# Wiring-Board-Nano.net
KiCad netlist of a schematic drawn in EAGLE
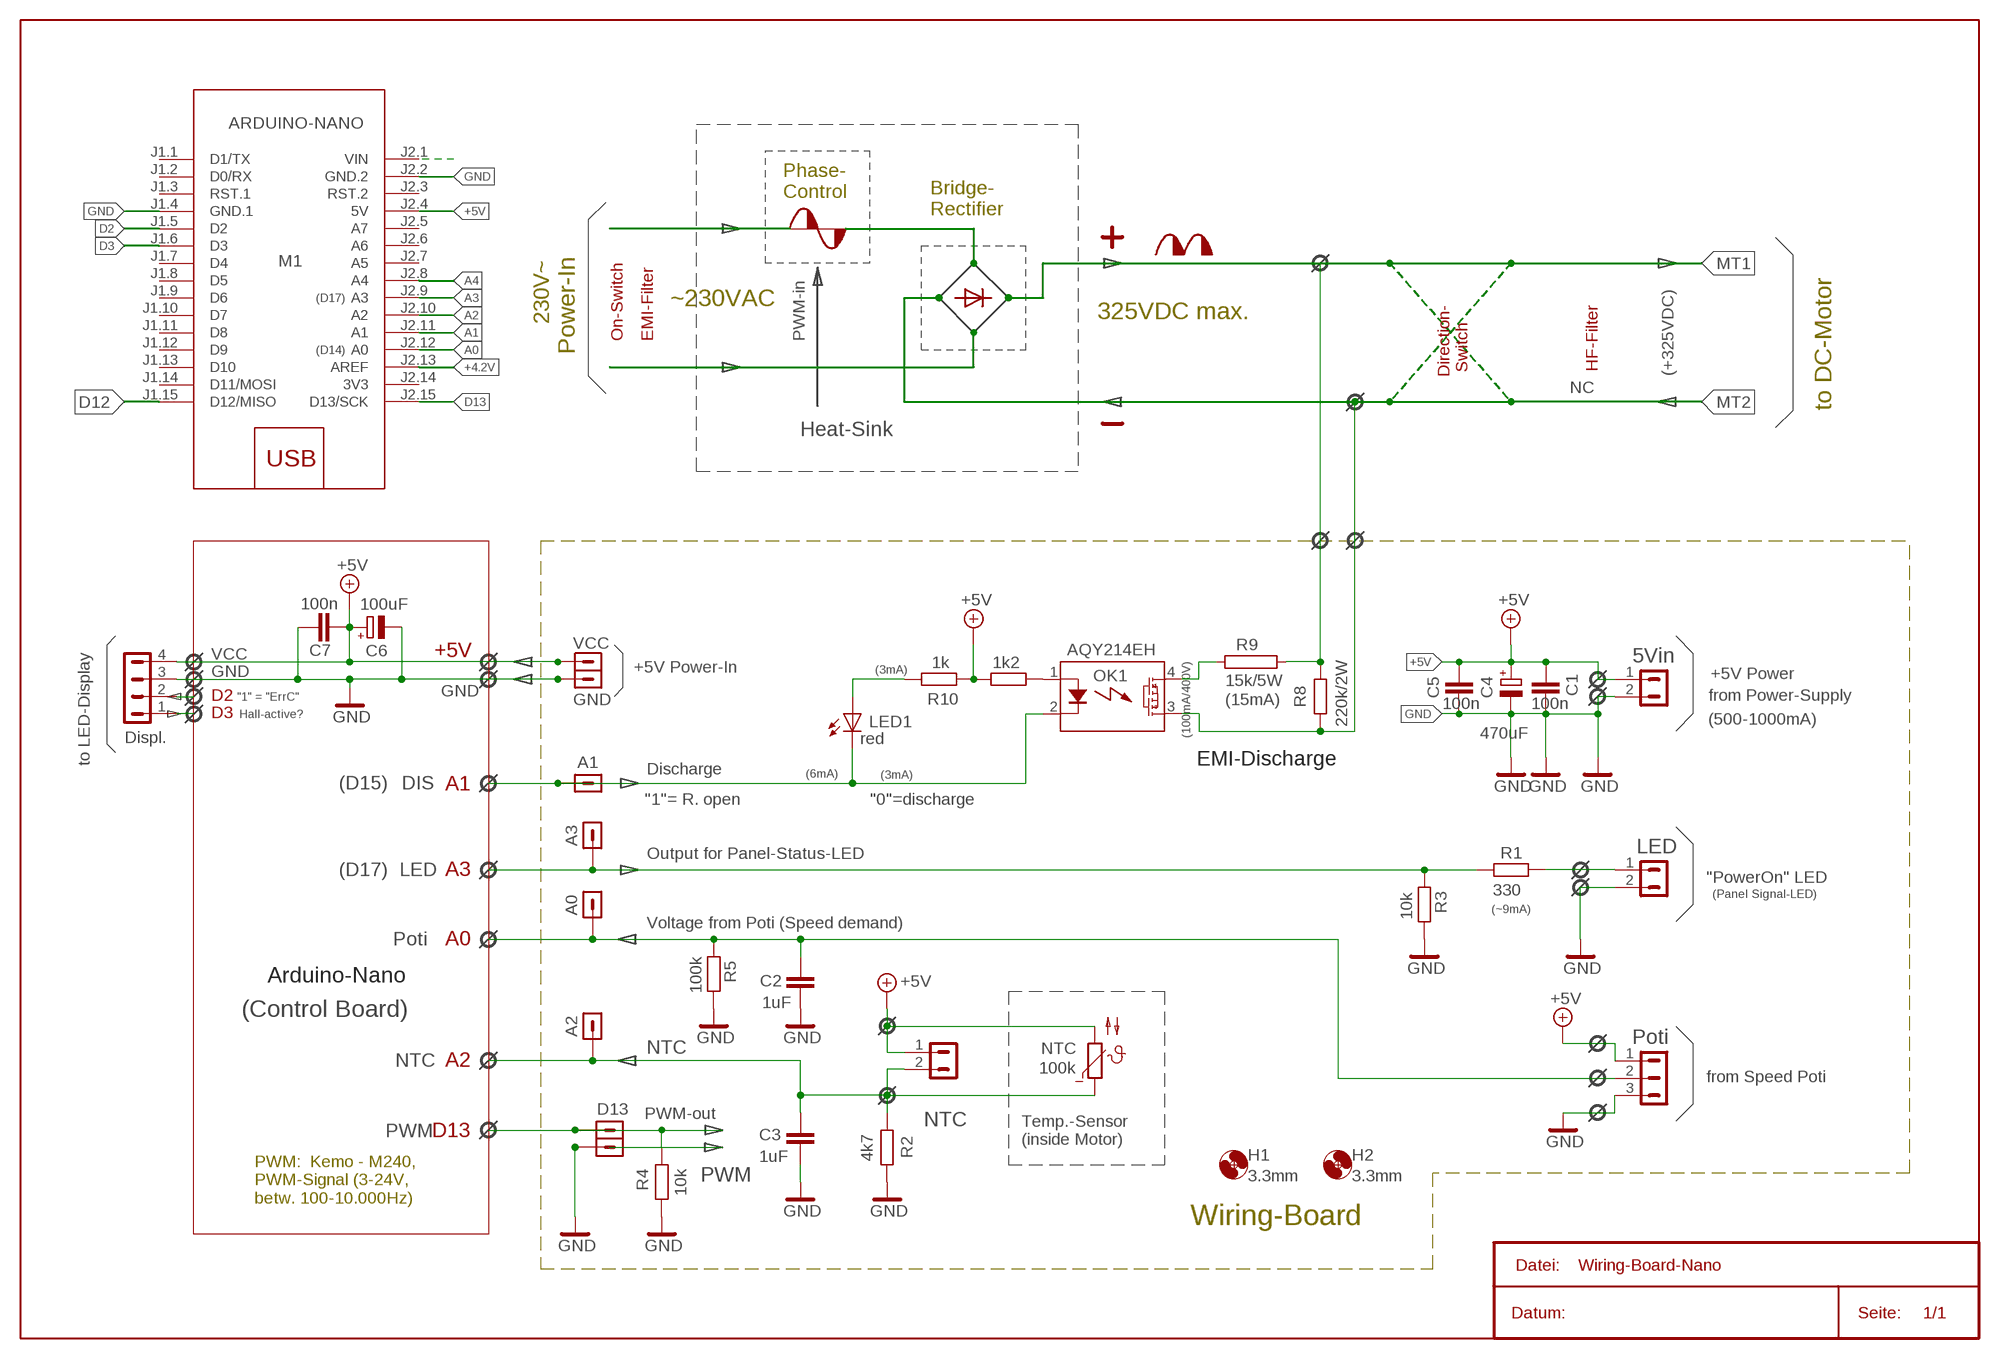
[diagram p0: schematic, sheet 1]

(export (version "E")
  (design (tool "Eeschema 10.0.6"))
  (components
    (comp (ref "C1")
      (value "100n")
      (footprint "eagle-import:C0805")
      (libsource (lib "eagle-import") (part "C-EUC0805"))
    )
    (comp (ref "C2")
      (value "1uF")
      (footprint "eagle-import:C0805")
      (libsource (lib "eagle-import") (part "C-EUC0805"))
    )
    (comp (ref "C3")
      (value "1uF")
      (footprint "eagle-import:C0805")
      (libsource (lib "eagle-import") (part "C-EUC0805"))
    )
    (comp (ref "C4")
      (value "470uF")
      (footprint "eagle-import:E3,5-8")
      (libsource (lib "eagle-import") (part "CPOL-EUE3.5-8"))
    )
    (comp (ref "C5")
      (value "100n")
      (footprint "eagle-import:C0805")
      (libsource (lib "eagle-import") (part "C-EUC0805"))
    )
    (comp (ref "C6")
      (value "100uF")
      (footprint "eagle-import:E2,5-7")
      (libsource (lib "eagle-import") (part "CPOL-EUE2.5-7"))
    )
    (comp (ref "C7")
      (value "100n")
      (footprint "eagle-import:C0805")
      (libsource (lib "eagle-import") (part "C-EUC0805"))
    )
    (comp (ref "H1")
      (value "3.3mm")
      (footprint "eagle-import:3,3")
      (libsource (lib "eagle-import") (part "MOUNT-HOLE3.3"))
    )
    (comp (ref "H2")
      (value "3.3mm")
      (footprint "eagle-import:3,3")
      (libsource (lib "eagle-import") (part "MOUNT-HOLE3.3"))
    )
    (comp (ref "LED1")
      (value "red")
      (footprint "eagle-import:CHIPLED_0805")
      (libsource (lib "eagle-import") (part "LEDCHIPLED_0805"))
    )
    (comp (ref "M1")
      (value "ARDUINO-NANO")
      (footprint "eagle-import:ARDUINO-NANO-3.0")
      (libsource (lib "eagle-import") (part "ARDUINO-NANO-3.0"))
    )
    (comp (ref "OK1")
      (value "AQY214EH")
      (footprint "eagle-import:GULLWING")
      (libsource (lib "eagle-import") (part "AQY"))
    )
    (comp (ref "R1")
      (value "330")
      (footprint "eagle-import:R0805")
      (libsource (lib "eagle-import") (part "R-EU_R0805"))
    )
    (comp (ref "R2")
      (value "4k7")
      (footprint "eagle-import:R0805")
      (libsource (lib "eagle-import") (part "R-EU_R0805"))
    )
    (comp (ref "R3")
      (value "10k")
      (footprint "eagle-import:R0805")
      (libsource (lib "eagle-import") (part "R-EU_R0805"))
    )
    (comp (ref "R4")
      (value "10k")
      (footprint "eagle-import:R0805")
      (libsource (lib "eagle-import") (part "R-EU_R0805"))
    )
    (comp (ref "R5")
      (value "100k")
      (footprint "eagle-import:R0805")
      (libsource (lib "eagle-import") (part "R-EU_R0805"))
    )
    (comp (ref "R8")
      (value "220k/2W")
      (footprint "eagle-import:0309_12")
      (libsource (lib "eagle-import") (part "R-EU_0309/12"))
    )
    (comp (ref "R9")
      (value "15k/5W")
      (footprint "eagle-import:KH206-8")
      (libsource (lib "eagle-import") (part "RKH206-8"))
    )
    (comp (ref "R10")
      (value "1k")
      (footprint "eagle-import:R0805")
      (libsource (lib "eagle-import") (part "R-EU_R0805"))
    )
    (comp (ref "R11")
      (value "1k2")
      (footprint "eagle-import:R0805")
      (libsource (lib "eagle-import") (part "R-EU_R0805"))
    )
    (comp (ref "SV1")
      (value "5Vin")
      (footprint "eagle-import:MA02-1")
      (libsource (lib "eagle-import") (part "MA02-10"))
    )
    (comp (ref "SV2")
      (value "LED")
      (footprint "eagle-import:MA02-1")
      (libsource (lib "eagle-import") (part "MA02-10"))
    )
    (comp (ref "SV3")
      (value "Poti")
      (footprint "eagle-import:MA03-1")
      (libsource (lib "eagle-import") (part "MA03-10"))
    )
    (comp (ref "SV4")
      (value "NTC")
      (footprint "eagle-import:MA02-1")
      (libsource (lib "eagle-import") (part "MA02-10"))
    )
    (comp (ref "SV6")
      (value "Displ.")
      (footprint "eagle-import:MA04-1")
      (libsource (lib "eagle-import") (part "MA04-10"))
    )
  )
  (nets
    (net (code "1") (name "+4.2V") (class "Default")
      (node (ref "M1") (pin "J2.13") (pinfunction "AREF_J2.13") (pintype "bidirectional"))
    )
    (net (code "2") (name "+5V") (class "Default")
      (node (ref "C1") (pin "1") (pinfunction "1_1") (pintype "passive"))
      (node (ref "C4") (pin "+") (pinfunction "+_+") (pintype "passive"))
      (node (ref "C5") (pin "1") (pinfunction "1_1") (pintype "passive"))
      (node (ref "C6") (pin "+") (pinfunction "+_+") (pintype "passive"))
      (node (ref "C7") (pin "1") (pinfunction "1_1") (pintype "passive"))
      (node (ref "M1") (pin "J2.4") (pinfunction "5V_J2.4") (pintype "power_in"))
      (node (ref "R10") (pin "2") (pinfunction "2_2") (pintype "passive"))
      (node (ref "R11") (pin "1") (pinfunction "1_1") (pintype "passive"))
      (node (ref "SV1") (pin "1") (pinfunction "1_1") (pintype "passive"))
      (node (ref "SV3") (pin "1") (pinfunction "1_1") (pintype "passive"))
      (node (ref "SV4") (pin "1") (pinfunction "1_1") (pintype "passive"))
      (node (ref "SV6") (pin "4") (pinfunction "4_4") (pintype "passive"))
    )
    (net (code "3") (name "/3V3") (class "Default")
      (node (ref "M1") (pin "J2.14") (pinfunction "3V3_J2.14") (pintype "power_in"))
    )
    (net (code "4") (name "A0") (class "Default")
      (node (ref "C2") (pin "1") (pinfunction "1_1") (pintype "passive"))
      (node (ref "M1") (pin "J2.12") (pinfunction "A0_J2.12") (pintype "bidirectional"))
      (node (ref "R5") (pin "1") (pinfunction "1_1") (pintype "passive"))
      (node (ref "SV3") (pin "2") (pinfunction "2_2") (pintype "passive"))
    )
    (net (code "5") (name "A1") (class "Default")
      (node (ref "LED1") (pin "C") (pinfunction "C_C") (pintype "passive"))
      (node (ref "M1") (pin "J2.11") (pinfunction "A1_J2.11") (pintype "bidirectional"))
      (node (ref "OK1") (pin "2") (pinfunction "K_2") (pintype "passive"))
    )
    (net (code "6") (name "A2") (class "Default")
      (node (ref "C3") (pin "1") (pinfunction "1_1") (pintype "passive"))
      (node (ref "M1") (pin "J2.10") (pinfunction "A2_J2.10") (pintype "bidirectional"))
      (node (ref "R2") (pin "2") (pinfunction "2_2") (pintype "passive"))
      (node (ref "SV4") (pin "2") (pinfunction "2_2") (pintype "passive"))
    )
    (net (code "7") (name "A3") (class "Default")
      (node (ref "M1") (pin "J2.9") (pinfunction "A3_J2.9") (pintype "bidirectional"))
      (node (ref "R1") (pin "1") (pinfunction "1_1") (pintype "passive"))
      (node (ref "R3") (pin "1") (pinfunction "1_1") (pintype "passive"))
    )
    (net (code "8") (name "A4") (class "Default")
      (node (ref "M1") (pin "J2.8") (pinfunction "A4_J2.8") (pintype "bidirectional"))
    )
    (net (code "9") (name "D2") (class "Default")
      (node (ref "M1") (pin "J1.5") (pinfunction "D2_J1.5") (pintype "bidirectional"))
      (node (ref "SV6") (pin "2") (pinfunction "2_2") (pintype "passive"))
    )
    (net (code "10") (name "D3") (class "Default")
      (node (ref "M1") (pin "J1.6") (pinfunction "D3_J1.6") (pintype "bidirectional"))
      (node (ref "SV6") (pin "1") (pinfunction "1_1") (pintype "passive"))
    )
    (net (code "11") (name "D12") (class "Default")
      (node (ref "M1") (pin "J1.15") (pinfunction "D12/MISO_J1.15") (pintype "bidirectional"))
    )
    (net (code "12") (name "D13") (class "Default")
      (node (ref "M1") (pin "J2.15") (pinfunction "D13/SCK_J2.15") (pintype "bidirectional"))
      (node (ref "R4") (pin "1") (pinfunction "1_1") (pintype "passive"))
    )
    (net (code "13") (name "GND") (class "Default")
      (node (ref "C1") (pin "2") (pinfunction "2_2") (pintype "passive"))
      (node (ref "C2") (pin "2") (pinfunction "2_2") (pintype "passive"))
      (node (ref "C3") (pin "2") (pinfunction "2_2") (pintype "passive"))
      (node (ref "C4") (pin "-") (pinfunction "-_-") (pintype "passive"))
      (node (ref "C5") (pin "2") (pinfunction "2_2") (pintype "passive"))
      (node (ref "C6") (pin "-") (pinfunction "-_-") (pintype "passive"))
      (node (ref "C7") (pin "2") (pinfunction "2_2") (pintype "passive"))
      (node (ref "M1") (pin "J1.4") (pinfunction "GND.1_J1.4") (pintype "power_in"))
      (node (ref "M1") (pin "J2.2") (pinfunction "GND.2_J2.2") (pintype "power_in"))
      (node (ref "R2") (pin "1") (pinfunction "1_1") (pintype "passive"))
      (node (ref "R3") (pin "2") (pinfunction "2_2") (pintype "passive"))
      (node (ref "R4") (pin "2") (pinfunction "2_2") (pintype "passive"))
      (node (ref "R5") (pin "2") (pinfunction "2_2") (pintype "passive"))
      (node (ref "SV1") (pin "2") (pinfunction "2_2") (pintype "passive"))
      (node (ref "SV2") (pin "2") (pinfunction "2_2") (pintype "passive"))
      (node (ref "SV3") (pin "3") (pinfunction "3_3") (pintype "passive"))
      (node (ref "SV6") (pin "3") (pinfunction "3_3") (pintype "passive"))
    )
    (net (code "14") (name "MT1") (class "Default")
      (node (ref "R8") (pin "2") (pinfunction "2_2") (pintype "passive"))
      (node (ref "R9") (pin "2") (pinfunction "2_2") (pintype "passive"))
    )
    (net (code "16") (name "Net-(LED1-PadA)") (class "Default")
      (node (ref "LED1") (pin "A") (pinfunction "A_A") (pintype "passive"))
      (node (ref "R10") (pin "1") (pinfunction "1_1") (pintype "passive"))
    )
    (net (code "17") (name "Net-(OK1-A)") (class "Default")
      (node (ref "OK1") (pin "1") (pinfunction "A_1") (pintype "passive"))
      (node (ref "R11") (pin "2") (pinfunction "2_2") (pintype "passive"))
    )
    (net (code "18") (name "Net-(OK1-DS1)") (class "Default")
      (node (ref "OK1") (pin "4") (pinfunction "DS1_4") (pintype "passive"))
      (node (ref "R9") (pin "1") (pinfunction "1_1") (pintype "passive"))
    )
    (net (code "19") (name "Net-(OK1-DS2)") (class "Default")
      (node (ref "OK1") (pin "3") (pinfunction "DS2_3") (pintype "passive"))
      (node (ref "R8") (pin "1") (pinfunction "1_1") (pintype "passive"))
    )
    (net (code "20") (name "Net-(R1-Pad2)") (class "Default")
      (node (ref "R1") (pin "2") (pinfunction "2_2") (pintype "passive"))
      (node (ref "SV2") (pin "1") (pinfunction "1_1") (pintype "passive"))
    )
    (net (code "21") (name "unconnected-(M1-A5-PadJ2.7)") (class "Default")
      (node (ref "M1") (pin "J2.7") (pinfunction "A5_J2.7") (pintype "bidirectional"))
    )
    (net (code "22") (name "unconnected-(M1-A6-PadJ2.6)") (class "Default")
      (node (ref "M1") (pin "J2.6") (pinfunction "A6_J2.6") (pintype "bidirectional"))
    )
    (net (code "23") (name "unconnected-(M1-A7-PadJ2.5)") (class "Default")
      (node (ref "M1") (pin "J2.5") (pinfunction "A7_J2.5") (pintype "bidirectional"))
    )
    (net (code "24") (name "unconnected-(M1-D0{slash}RX-PadJ1.2)") (class "Default")
      (node (ref "M1") (pin "J1.2") (pinfunction "D0/RX_J1.2") (pintype "bidirectional"))
    )
    (net (code "25") (name "unconnected-(M1-D1{slash}TX-PadJ1.1)") (class "Default")
      (node (ref "M1") (pin "J1.1") (pinfunction "D1/TX_J1.1") (pintype "bidirectional"))
    )
    (net (code "26") (name "unconnected-(M1-D4-PadJ1.7)") (class "Default")
      (node (ref "M1") (pin "J1.7") (pinfunction "D4_J1.7") (pintype "bidirectional"))
    )
    (net (code "27") (name "unconnected-(M1-D5-PadJ1.8)") (class "Default")
      (node (ref "M1") (pin "J1.8") (pinfunction "D5_J1.8") (pintype "bidirectional"))
    )
    (net (code "28") (name "unconnected-(M1-D6-PadJ1.9)") (class "Default")
      (node (ref "M1") (pin "J1.9") (pinfunction "D6_J1.9") (pintype "bidirectional"))
    )
    (net (code "29") (name "unconnected-(M1-D7-PadJ1.10)") (class "Default")
      (node (ref "M1") (pin "J1.10") (pinfunction "D7_J1.10") (pintype "bidirectional"))
    )
    (net (code "30") (name "unconnected-(M1-D8-PadJ1.11)") (class "Default")
      (node (ref "M1") (pin "J1.11") (pinfunction "D8_J1.11") (pintype "bidirectional"))
    )
    (net (code "31") (name "unconnected-(M1-D9-PadJ1.12)") (class "Default")
      (node (ref "M1") (pin "J1.12") (pinfunction "D9_J1.12") (pintype "bidirectional"))
    )
    (net (code "32") (name "unconnected-(M1-D10-PadJ1.13)") (class "Default")
      (node (ref "M1") (pin "J1.13") (pinfunction "D10_J1.13") (pintype "bidirectional"))
    )
    (net (code "33") (name "unconnected-(M1-D11{slash}MOSI-PadJ1.14)") (class "Default")
      (node (ref "M1") (pin "J1.14") (pinfunction "D11/MOSI_J1.14") (pintype "bidirectional"))
    )
    (net (code "34") (name "unconnected-(M1-RST.1-PadJ1.3)") (class "Default")
      (node (ref "M1") (pin "J1.3") (pinfunction "RST.1_J1.3") (pintype "bidirectional"))
    )
    (net (code "35") (name "unconnected-(M1-RST.2-PadJ2.3)") (class "Default")
      (node (ref "M1") (pin "J2.3") (pinfunction "RST.2_J2.3") (pintype "bidirectional"))
    )
    (net (code "36") (name "unconnected-(M1-VIN-PadJ2.1)") (class "Default")
      (node (ref "M1") (pin "J2.1") (pinfunction "VIN_J2.1") (pintype "power_in"))
    )
  )
)
